# design.net
KiCad netlist of a schematic drawn in Altium Designer
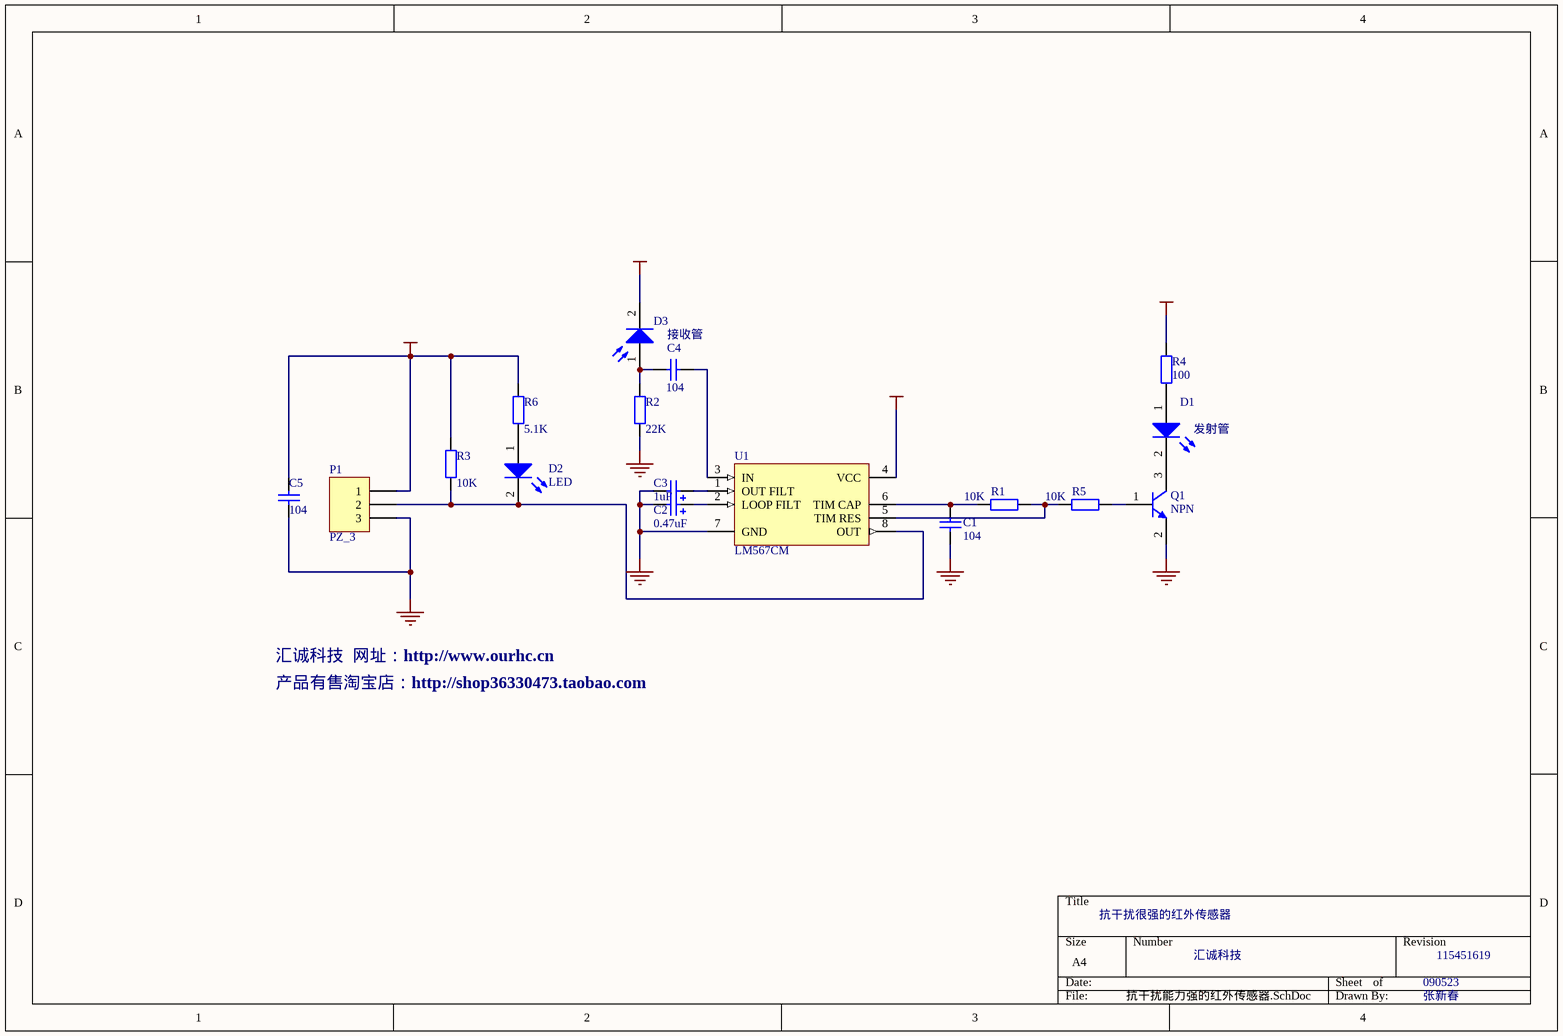
[diagram p0: 抗干扰能力强的红外传感器.SchDoc]

(export (version "E")
  (design (tool "Eeschema 10.0.6"))
  (components
    (comp (ref "C1")
      (value "104")
      (footprint "TP-0805-R")
      (description "瓷片电容")
      (fields (field (name "PUBLISHER") "Altium Limited"))
      (libsource (lib "zxcourhc") (part "CPDR"))
    )
    (comp (ref "C2")
      (value "0.47uF")
      (footprint "DJDR_4mm")
      (description "电解电容")
      (fields (field (name "PUBLISHER") "Altium Limited"))
      (libsource (lib "zxcourhc") (part "DJDR"))
    )
    (comp (ref "C3")
      (value "1uF")
      (footprint "DJDR_4mm")
      (description "电解电容")
      (fields (field (name "PUBLISHER") "Altium Limited"))
      (libsource (lib "zxcourhc") (part "DJDR"))
    )
    (comp (ref "C4")
      (value "104")
      (footprint "TP-0805-R")
      (description "瓷片电容")
      (fields (field (name "PUBLISHER") "Altium Limited"))
      (libsource (lib "zxcourhc") (part "CPDR"))
    )
    (comp (ref "C5")
      (value "104")
      (footprint "TP-0805-R")
      (description "瓷片电容")
      (fields (field (name "PUBLISHER") "Altium Limited"))
      (libsource (lib "zxcourhc") (part "CPDR"))
    )
    (comp (ref "D1")
      (value "发射管")
      (footprint "CPDR")
      (description "发光二极管")
      (fields (field (name "PUBLISHER") "Altium Limited"))
      (libsource (lib "zxcourhc") (part "LED"))
    )
    (comp (ref "D2")
      (value "LED")
      (footprint "CPDR")
      (description "发光二极管")
      (fields (field (name "PUBLISHER") "Altium Limited"))
      (libsource (lib "zxcourhc") (part "LED"))
    )
    (comp (ref "D3")
      (value "接收管")
      (footprint "CPDR")
      (description "接收二极管")
      (fields (field (name "PUBLISHER") "Altium Limited"))
      (libsource (lib "zxcourhc") (part "JS2JG"))
    )
    (comp (ref "P1")
      (value "PZ_3")
      (footprint "HDR-3")
      (description "排针——3")
      (fields (field (name "PUBLISHER") "Altium Limited"))
      (libsource (lib "zxcourhc") (part "PZ_3"))
    )
    (comp (ref "Q1")
      (value "NPN")
      (footprint "SO-G3")
      (description "贴片三极管——NPN")
      (fields (field (name "PUBLISHER") "Altium Limited"))
      (libsource (lib "zxcourhc") (part "TPSJG_NPN"))
    )
    (comp (ref "R1")
      (value "10K")
      (footprint "TP-0805-R")
      (description "电阻")
      (fields (field (name "PUBLISHER") "Altium Limited"))
      (libsource (lib "") (part "Res_1"))
    )
    (comp (ref "R2")
      (value "22K")
      (footprint "TP-0805-R")
      (description "电阻")
      (fields (field (name "PUBLISHER") "Altium Limited"))
      (libsource (lib "") (part "Res_2"))
    )
    (comp (ref "R3")
      (value "10K")
      (footprint "TP-0805-R")
      (description "电阻")
      (fields (field (name "PUBLISHER") "Altium Limited"))
      (libsource (lib "") (part "Res_2"))
    )
    (comp (ref "R4")
      (value "100")
      (footprint "TP-0805-R")
      (description "电阻")
      (fields (field (name "PUBLISHER") "Altium Limited"))
      (libsource (lib "zxcourhc") (part "Res"))
    )
    (comp (ref "R5")
      (value "10K")
      (footprint "TP-0805-R")
      (description "电阻")
      (fields (field (name "PUBLISHER") "Altium Limited"))
      (libsource (lib "") (part "Res_1"))
    )
    (comp (ref "R6")
      (value "5.1K")
      (footprint "TP-0805-R")
      (description "电阻")
      (fields (field (name "PUBLISHER") "Altium Limited"))
      (libsource (lib "") (part "Res_2"))
    )
    (comp (ref "U1")
      (value "LM567CM")
      (footprint "M08A")
      (description "Tone Decoder")
      (fields (field (name "PUBLISHER") "Altium Limited"))
      (libsource (lib "NSC Logic Decoder Demux") (part "LM567CM"))
    )
  )
  (nets
    (net (code "1") (name "GND") (class "Default")
      (node (ref "C1") (pin "2") (pinfunction "2_2") (pintype "passive"))
      (node (ref "C2") (pin "2") (pinfunction "2_2") (pintype "passive"))
      (node (ref "C3") (pin "2") (pinfunction "2_2") (pintype "passive"))
      (node (ref "C5") (pin "1") (pinfunction "1_1") (pintype "passive"))
      (node (ref "P1") (pin "3") (pinfunction "3_3") (pintype "passive"))
      (node (ref "Q1") (pin "2") (pinfunction "E_2") (pintype "passive"))
      (node (ref "R2") (pin "1") (pinfunction "1_1") (pintype "passive"))
      (node (ref "U1") (pin "7") (pinfunction "GND_7") (pintype "power_in"))
    )
    (net (code "2") (name "Net-(D1-A)") (class "Default")
      (node (ref "D1") (pin "1") (pinfunction "A_1") (pintype "passive"))
      (node (ref "R4") (pin "2") (pinfunction "2_2") (pintype "passive"))
    )
    (net (code "3") (name "Net-(D1-K)") (class "Default")
      (node (ref "D1") (pin "2") (pinfunction "K_2") (pintype "passive"))
      (node (ref "Q1") (pin "3") (pinfunction "C_3") (pintype "passive"))
    )
    (net (code "4") (name "Net-(D2-A)") (class "Default")
      (node (ref "D2") (pin "1") (pinfunction "A_1") (pintype "passive"))
      (node (ref "R6") (pin "1") (pinfunction "1_1") (pintype "passive"))
    )
    (net (code "5") (name "Net-(D2-K)") (class "Default")
      (node (ref "D2") (pin "2") (pinfunction "K_2") (pintype "passive"))
      (node (ref "P1") (pin "2") (pinfunction "2_2") (pintype "passive"))
      (node (ref "R3") (pin "1") (pinfunction "1_1") (pintype "passive"))
      (node (ref "U1") (pin "8") (pinfunction "OUT_8") (pintype "output"))
    )
    (net (code "6") (name "Net-(D3-A)") (class "Default")
      (node (ref "C4") (pin "2") (pinfunction "2_2") (pintype "passive"))
      (node (ref "D3") (pin "1") (pinfunction "A_1") (pintype "passive"))
      (node (ref "R2") (pin "2") (pinfunction "2_2") (pintype "passive"))
    )
    (net (code "7") (name "Net-(Q1-B)") (class "Default")
      (node (ref "Q1") (pin "1") (pinfunction "B_1") (pintype "passive"))
      (node (ref "R5") (pin "1") (pinfunction "1_1") (pintype "passive"))
    )
    (net (code "8") (name "Net-(U1-IN)") (class "Default")
      (node (ref "C4") (pin "1") (pinfunction "1_1") (pintype "passive"))
      (node (ref "U1") (pin "3") (pinfunction "IN_3") (pintype "input"))
    )
    (net (code "9") (name "Net-(U1-LOOP_FILT)") (class "Default")
      (node (ref "C2") (pin "1") (pinfunction "1_1") (pintype "passive"))
      (node (ref "U1") (pin "2") (pinfunction "LOOP_FILT_2") (pintype "input"))
    )
    (net (code "10") (name "Net-(U1-OUT_FILT)") (class "Default")
      (node (ref "C3") (pin "1") (pinfunction "1_1") (pintype "passive"))
      (node (ref "U1") (pin "1") (pinfunction "OUT_FILT_1") (pintype "input"))
    )
    (net (code "11") (name "Net-(U1-TIM_CAP)") (class "Default")
      (node (ref "C1") (pin "1") (pinfunction "1_1") (pintype "passive"))
      (node (ref "R1") (pin "2") (pinfunction "2_2") (pintype "passive"))
      (node (ref "U1") (pin "6") (pinfunction "TIM_CAP_6") (pintype "passive"))
    )
    (net (code "12") (name "Net-(U1-TIM_RES)") (class "Default")
      (node (ref "R1") (pin "1") (pinfunction "1_1") (pintype "passive"))
      (node (ref "R5") (pin "2") (pinfunction "2_2") (pintype "passive"))
      (node (ref "U1") (pin "5") (pinfunction "TIM_RES_5") (pintype "passive"))
    )
    (net (code "13") (name "VCC") (class "Default")
      (node (ref "C5") (pin "2") (pinfunction "2_2") (pintype "passive"))
      (node (ref "D3") (pin "2") (pinfunction "K_2") (pintype "passive"))
      (node (ref "P1") (pin "1") (pinfunction "1_1") (pintype "passive"))
      (node (ref "R3") (pin "2") (pinfunction "2_2") (pintype "passive"))
      (node (ref "R4") (pin "1") (pinfunction "1_1") (pintype "passive"))
      (node (ref "R6") (pin "2") (pinfunction "2_2") (pintype "passive"))
      (node (ref "U1") (pin "4") (pinfunction "VCC_4") (pintype "power_in"))
    )
  )
)
